# Data_Connector.net
KiCad netlist of a schematic drawn in Altium Designer
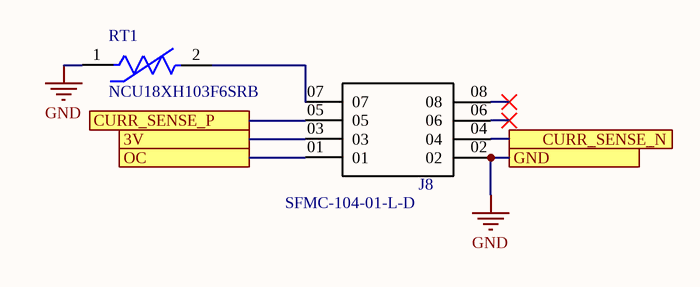
[diagram p0: Data Connector.SchDoc]

(export (version "E")
  (design (tool "Eeschema 10.0.6"))
  (components
    (comp (ref "J8")
      (value "SFMC-104-01-L-D")
      (footprint "*SAMTEC_SFMC-104-01-L-D_SFMC-104-01-L-D(Primary)")
      (libsource (lib "Schlib1") (part "SFMC-104-01-L-D"))
    )
    (comp (ref "RT1")
      (value "NCU18XH103F6SRB")
      (footprint "FP-NCU18-0_15-IPC_B")
      (description "THERMISTOR NTC")
      (libsource (lib "Altium Content Vault") (part "3b148a6ebabc5fb4d708a66c052d352"))
    )
  )
  (nets
    (net (code "1") (name "/3V") (class "Default")
      (node (ref "J8") (pin "03") (pinfunction "03_03") (pintype "passive"))
    )
    (net (code "2") (name "/CURR_SENSE_N") (class "Default")
      (node (ref "J8") (pin "04") (pinfunction "04_04") (pintype "passive"))
    )
    (net (code "3") (name "/CURR_SENSE_P") (class "Default")
      (node (ref "J8") (pin "05") (pinfunction "05_05") (pintype "passive"))
    )
    (net (code "4") (name "/OC") (class "Default")
      (node (ref "J8") (pin "01") (pinfunction "01_01") (pintype "passive"))
    )
    (net (code "5") (name "GND") (class "Default")
      (node (ref "J8") (pin "02") (pinfunction "02_02") (pintype "passive"))
      (node (ref "RT1") (pin "1") (pinfunction "1_1") (pintype "passive"))
    )
    (net (code "6") (name "Net-(J8-Pad07)") (class "Default")
      (node (ref "J8") (pin "07") (pinfunction "07_07") (pintype "passive"))
      (node (ref "RT1") (pin "2") (pinfunction "2_2") (pintype "passive"))
    )
    (net (code "7") (name "unconnected-(J8-Pad06)") (class "Default")
      (node (ref "J8") (pin "06") (pinfunction "06_06") (pintype "passive+no_connect"))
    )
    (net (code "8") (name "unconnected-(J8-Pad08)") (class "Default")
      (node (ref "J8") (pin "08") (pinfunction "08_08") (pintype "passive+no_connect"))
    )
  )
)
